# Robot-Main.net
KiCad netlist of a schematic drawn in Altium Designer
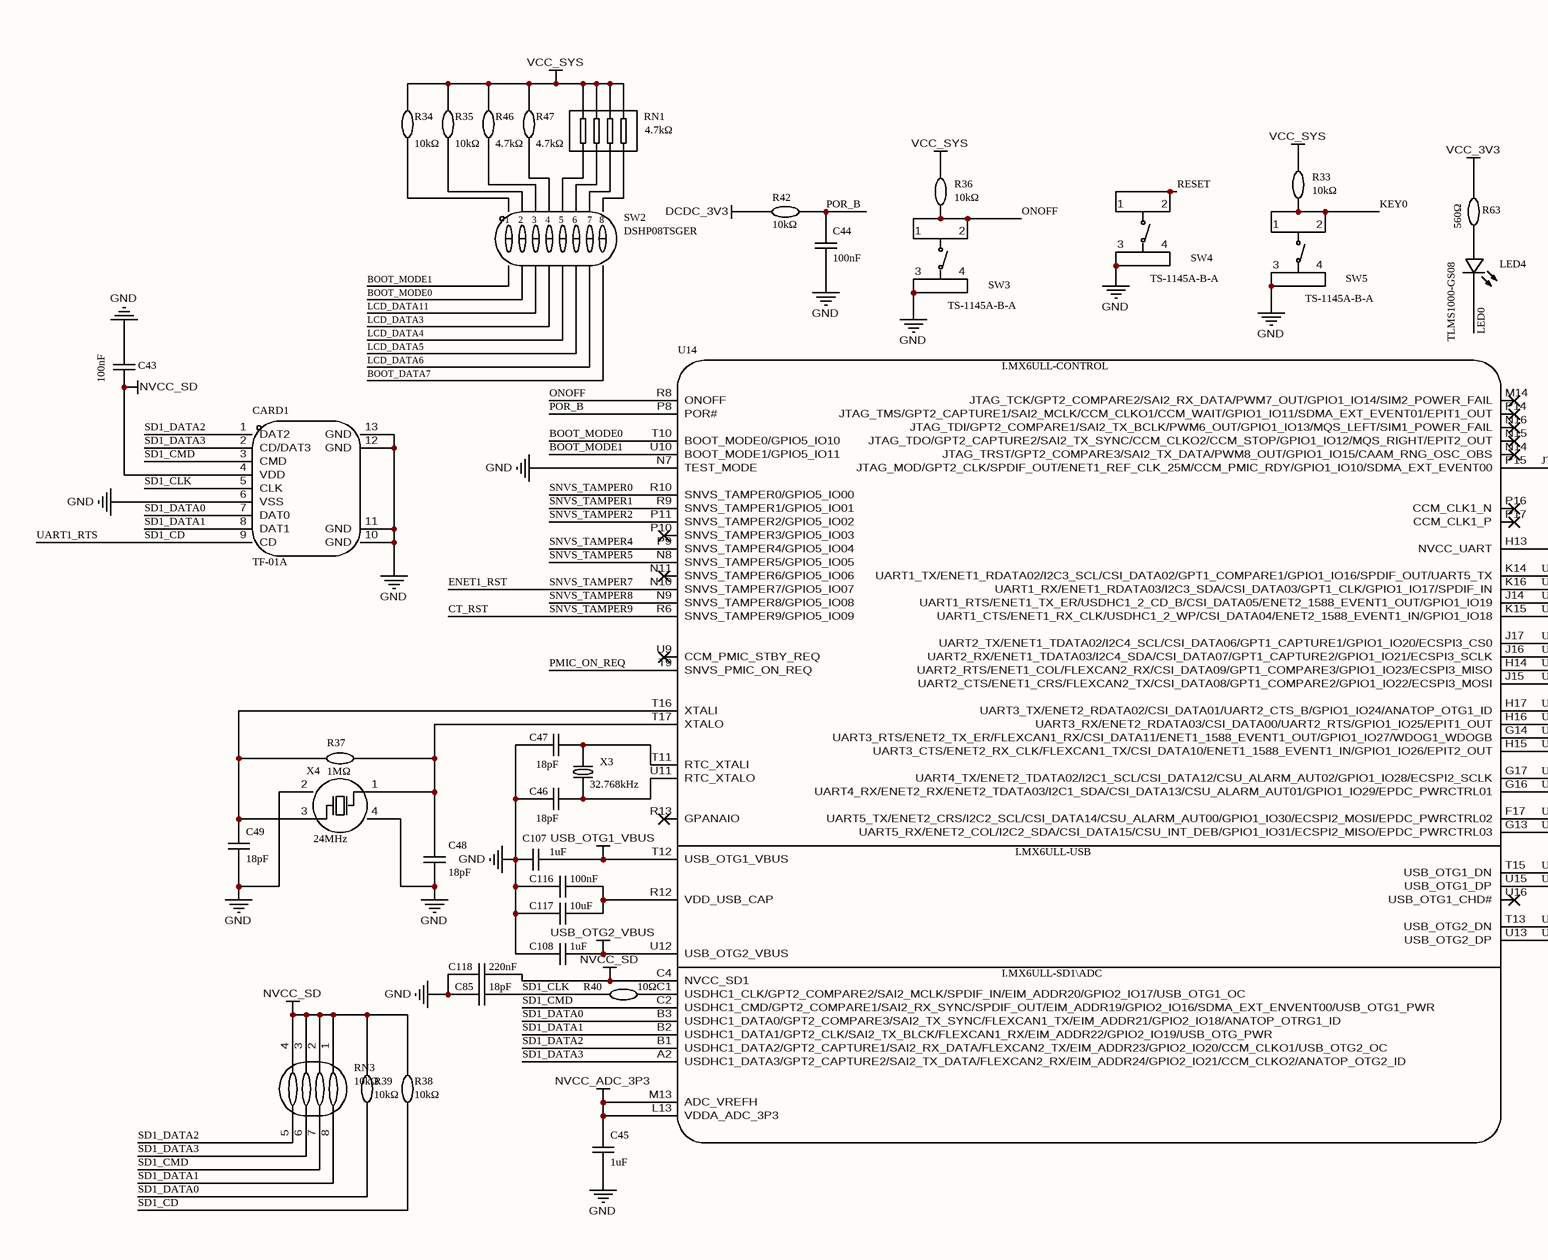
[diagram p0: Robot-Main.schdoc, left]
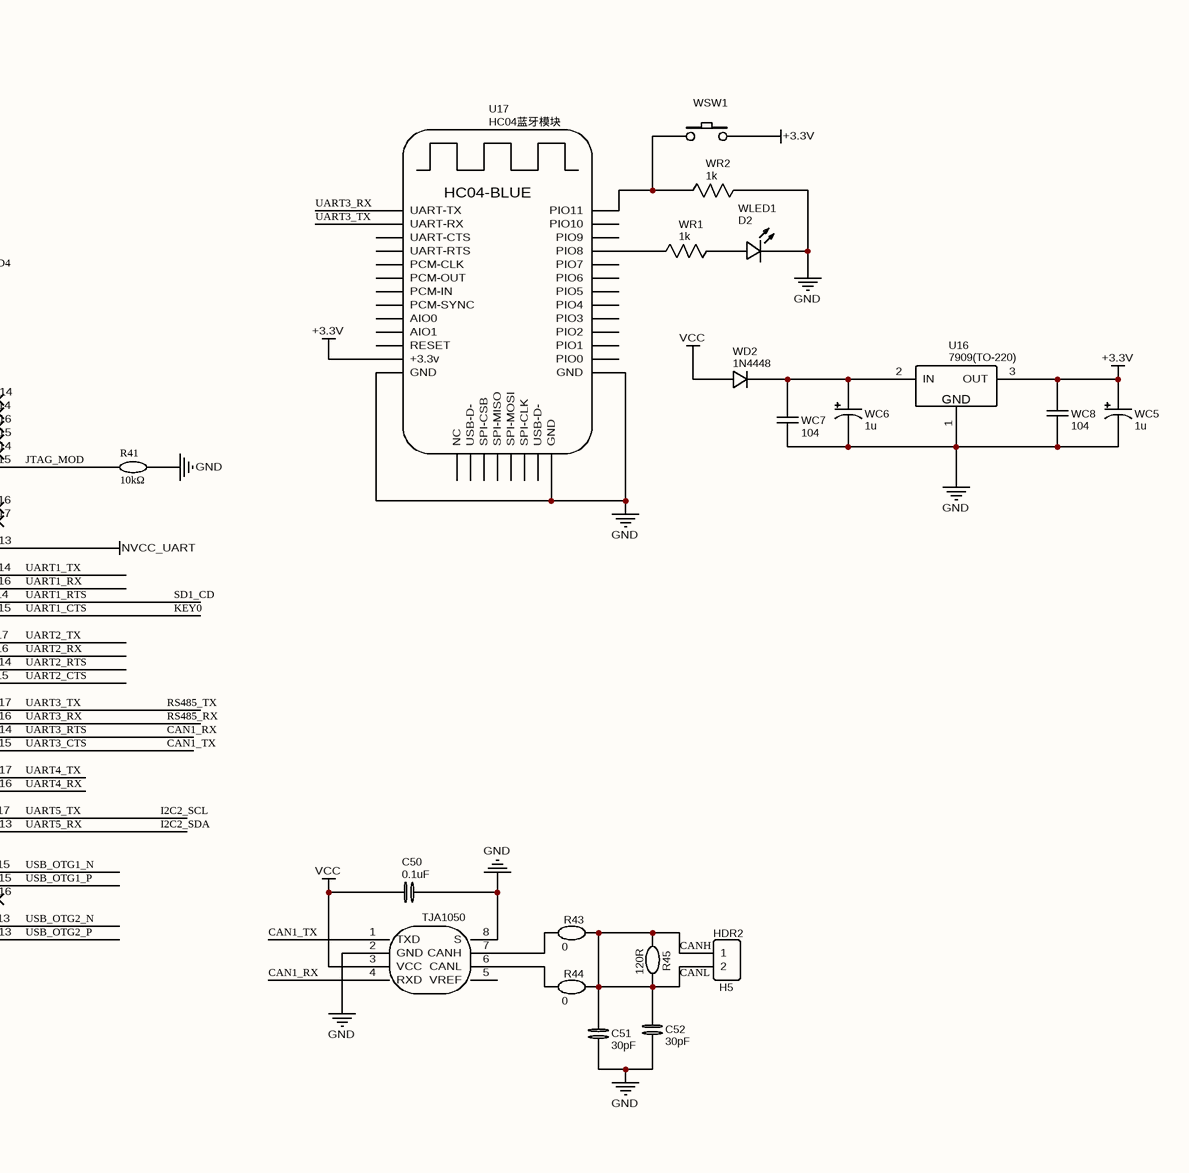
[diagram p1: Robot-Main.schdoc, right]

(export (version "E")
  (design (tool "Eeschema 10.0.6"))
  (components
    (comp (ref "C43")
      (value "100nF")
      (footprint "0")
      (fields
        (field (name "MANUFACTURER") "FH(风华)")
        (field (name "MANUFACTURER PART") "0402B104K160NT")
        (field (name "TOLERANCE") "±10%")
      )
      (libsource (lib "altium-import") (part "root_3_100nF_"))
    )
    (comp (ref "C44")
      (value "100nF")
      (footprint "0")
      (fields
        (field (name "MANUFACTURER") "FH(风华)")
        (field (name "MANUFACTURER PART") "0402B104K160NT")
        (field (name "TOLERANCE") "±10%")
      )
      (libsource (lib "altium-import") (part "root_3_100nF_"))
    )
    (comp (ref "C45")
      (value "1uF")
      (footprint "0")
      (fields
        (field (name "MANUFACTURER") "SAMSUNG(三星)")
        (field (name "MANUFACTURER PART") "CL05A105KP5NNNC")
        (field (name "TOLERANCE") "±10%")
      )
      (libsource (lib "altium-import") (part "root_1_1uF_"))
    )
    (comp (ref "C46")
      (value "18pF")
      (footprint "0")
      (fields
        (field (name "MANUFACTURER") "muRata(村田)")
        (field (name "MANUFACTURER PART") "GRM1555C1H180JA01D")
        (field (name "TOLERANCE") "±5%")
      )
      (libsource (lib "altium-import") (part "root_2_18pF_"))
    )
    (comp (ref "C47")
      (value "18pF")
      (footprint "0")
      (fields
        (field (name "MANUFACTURER") "muRata(村田)")
        (field (name "MANUFACTURER PART") "GRM1555C1H180JA01D")
        (field (name "TOLERANCE") "±5%")
      )
      (libsource (lib "altium-import") (part "root_2_18pF_"))
    )
    (comp (ref "C48")
      (value "18pF")
      (footprint "0")
      (fields
        (field (name "MANUFACTURER") "muRata(村田)")
        (field (name "MANUFACTURER PART") "GRM1555C1H180JA01D")
        (field (name "TOLERANCE") "±5%")
      )
      (libsource (lib "altium-import") (part "root_1_18pF_"))
    )
    (comp (ref "C49")
      (value "18pF")
      (footprint "0")
      (fields
        (field (name "MANUFACTURER") "muRata(村田)")
        (field (name "MANUFACTURER PART") "GRM1555C1H180JA01D")
        (field (name "TOLERANCE") "±5%")
      )
      (libsource (lib "altium-import") (part "root_1_18pF_"))
    )
    (comp (ref "C50")
      (value "0.1uF")
      (footprint "C0603")
      (fields (field (name "CONTRIBUTOR") "LCEDA_Lib"))
      (libsource (lib "altium-import") (part "root_0_0.1uF_"))
    )
    (comp (ref "C51")
      (value "30pF")
      (footprint "C0603")
      (fields (field (name "CONTRIBUTOR") "LCEDA_Lib"))
      (libsource (lib "altium-import") (part "root_1_30pF_"))
    )
    (comp (ref "C52")
      (value "30pF")
      (footprint "C0603")
      (fields (field (name "CONTRIBUTOR") "LCEDA_Lib"))
      (libsource (lib "altium-import") (part "root_1_30pF_"))
    )
    (comp (ref "C85")
      (value "18pF")
      (footprint "0")
      (fields
        (field (name "MANUFACTURER") "muRata(村田)")
        (field (name "MANUFACTURER PART") "GRM1555C1H180JA01D")
        (field (name "TOLERANCE") "±5%")
      )
      (libsource (lib "altium-import") (part "root_2_18pF_"))
    )
    (comp (ref "C107")
      (value "1uF")
      (footprint "0")
      (fields
        (field (name "MANUFACTURER") "SAMSUNG(三星)")
        (field (name "MANUFACTURER PART") "CL05A105KP5NNNC")
        (field (name "TOLERANCE") "±10%")
      )
      (libsource (lib "altium-import") (part "root_2_1uF_"))
    )
    (comp (ref "C108")
      (value "1uF")
      (footprint "0")
      (fields
        (field (name "MANUFACTURER") "SAMSUNG(三星)")
        (field (name "MANUFACTURER PART") "CL05A105KP5NNNC")
        (field (name "TOLERANCE") "±10%")
      )
      (libsource (lib "altium-import") (part "root_2_1uF_"))
    )
    (comp (ref "C116")
      (value "100nF")
      (footprint "0")
      (fields
        (field (name "MANUFACTURER") "FH(风华)")
        (field (name "MANUFACTURER PART") "0402B104K160NT")
        (field (name "TOLERANCE") "±10%")
      )
      (libsource (lib "altium-import") (part "root_0_100nF_"))
    )
    (comp (ref "C117")
      (value "10uF")
      (footprint "0")
      (fields
        (field (name "MANUFACTURER") "TAIYO YUDEN(太诱)")
        (field (name "MANUFACTURER PART") "JMK107BC6106MA-T")
        (field (name "TOLERANCE") "±20%")
      )
      (libsource (lib "altium-import") (part "root_2_10uF_"))
    )
    (comp (ref "C118")
      (value "220nF")
      (footprint "0")
      (fields
        (field (name "MANUFACTURER") "SAMSUNG(三星)")
        (field (name "MANUFACTURER PART") "CL05B224KO5NNNC")
        (field (name "TOLERANCE") "±10%")
      )
      (libsource (lib "altium-import") (part "root_2_220nF_"))
    )
    (comp (ref "CARD1")
      (value "TF-01A")
      (footprint "0")
      (fields (field (name "MANUFACTURER") "Yuandi(元迪)"))
      (libsource (lib "altium-import") (part "root_0_TF-01A_"))
    )
    (comp (ref "H5")
      (value "HDR2")
      (footprint "HDR-F-2.54_1X2")
      (fields (field (name "CONTRIBUTOR") "LCEDA_Lib"))
      (libsource (lib "altium-import") (part "root_0_HDR2_"))
    )
    (comp (ref "LED4")
      (value "TLMS1000-GS08")
      (footprint "0")
      (fields (field (name "MANUFACTURER") "VISHAY(威世)"))
      (libsource (lib "altium-import") (part "root_3_TLMS1000-GS08_"))
    )
    (comp (ref "R33")
      (value "10kΩ")
      (footprint "0")
      (fields
        (field (name "MANUFACTURER") "YAGEO(国巨)")
        (field (name "MANUFACTURER PART") "AC0402FR-0710KL")
        (field (name "TOLERANCE") "±1%")
      )
      (libsource (lib "altium-import") (part "root_3_10kΩ_"))
    )
    (comp (ref "R34")
      (value "10kΩ")
      (footprint "0")
      (fields
        (field (name "MANUFACTURER") "YAGEO(国巨)")
        (field (name "MANUFACTURER PART") "AC0402FR-0710KL")
        (field (name "TOLERANCE") "±1%")
      )
      (libsource (lib "altium-import") (part "root_1_10kΩ_"))
    )
    (comp (ref "R35")
      (value "10kΩ")
      (footprint "0")
      (fields
        (field (name "MANUFACTURER") "YAGEO(国巨)")
        (field (name "MANUFACTURER PART") "AC0402FR-0710KL")
        (field (name "TOLERANCE") "±1%")
      )
      (libsource (lib "altium-import") (part "root_1_10kΩ_"))
    )
    (comp (ref "R36")
      (value "10kΩ")
      (footprint "0")
      (fields
        (field (name "MANUFACTURER") "YAGEO(国巨)")
        (field (name "MANUFACTURER PART") "AC0402FR-0710KL")
        (field (name "TOLERANCE") "±1%")
      )
      (libsource (lib "altium-import") (part "root_3_10kΩ_"))
    )
    (comp (ref "R37")
      (value "1MΩ")
      (footprint "0")
      (fields
        (field (name "MANUFACTURER") "RESI(开步睿思）")
        (field (name "MANUFACTURER PART") "AECR0402F1M00K9")
        (field (name "TOLERANCE") "±1%")
      )
      (libsource (lib "altium-import") (part "root_0_1MΩ_"))
    )
    (comp (ref "R38")
      (value "10kΩ")
      (footprint "0")
      (fields
        (field (name "MANUFACTURER") "YAGEO(国巨)")
        (field (name "MANUFACTURER PART") "AC0402FR-0710KL")
        (field (name "TOLERANCE") "±1%")
      )
      (libsource (lib "altium-import") (part "root_1_10kΩ_"))
    )
    (comp (ref "R39")
      (value "10kΩ")
      (footprint "0")
      (fields
        (field (name "MANUFACTURER") "YAGEO(国巨)")
        (field (name "MANUFACTURER PART") "AC0402FR-0710KL")
        (field (name "TOLERANCE") "±1%")
      )
      (libsource (lib "altium-import") (part "root_1_10kΩ_"))
    )
    (comp (ref "R40")
      (value "10Ω")
      (footprint "0")
      (fields
        (field (name "MANUFACTURER") "YAGEO(国巨)")
        (field (name "MANUFACTURER PART") "RC0402FR-0710RL")
        (field (name "TOLERANCE") "±1%")
      )
      (libsource (lib "altium-import") (part "root_0_10Ω_"))
    )
    (comp (ref "R41")
      (value "10kΩ")
      (footprint "0")
      (fields
        (field (name "MANUFACTURER") "YAGEO(国巨)")
        (field (name "MANUFACTURER PART") "AC0402FR-0710KL")
        (field (name "TOLERANCE") "±1%")
      )
      (libsource (lib "altium-import") (part "root_2_10kΩ_"))
    )
    (comp (ref "R42")
      (value "10kΩ")
      (footprint "0")
      (fields
        (field (name "MANUFACTURER") "YAGEO(国巨)")
        (field (name "MANUFACTURER PART") "AC0402FR-0710KL")
        (field (name "TOLERANCE") "±1%")
      )
      (libsource (lib "altium-import") (part "root_2_10kΩ_"))
    )
    (comp (ref "R43")
      (value "0")
      (footprint "R0603")
      (fields (field (name "CONTRIBUTOR") "LCEDA_Lib"))
      (libsource (lib "altium-import") (part "root_0_0_"))
    )
    (comp (ref "R44")
      (value "0")
      (footprint "R0603")
      (fields (field (name "CONTRIBUTOR") "LCEDA_Lib"))
      (libsource (lib "altium-import") (part "root_0_0_"))
    )
    (comp (ref "R45")
      (value "120R")
      (footprint "R0603")
      (fields (field (name "CONTRIBUTOR") "LCEDA_Lib"))
      (libsource (lib "altium-import") (part "root_1_120R_"))
    )
    (comp (ref "R46")
      (value "4.7kΩ")
      (footprint "0")
      (fields
        (field (name "MANUFACTURER") "UNI-ROYAL(厚声)")
        (field (name "MANUFACTURER PART") "0402WGF4701TCE")
        (field (name "TOLERANCE") "±1%")
      )
      (libsource (lib "altium-import") (part "root_1_4.7kΩ_"))
    )
    (comp (ref "R47")
      (value "4.7kΩ")
      (footprint "0")
      (fields
        (field (name "MANUFACTURER") "UNI-ROYAL(厚声)")
        (field (name "MANUFACTURER PART") "0402WGF4701TCE")
        (field (name "TOLERANCE") "±1%")
      )
      (libsource (lib "altium-import") (part "root_1_4.7kΩ_"))
    )
    (comp (ref "R63")
      (value "560Ω")
      (footprint "0")
      (fields
        (field (name "MANUFACTURER") "PANASONIC(松下)")
        (field (name "MANUFACTURER PART") "ERJ2RKF5600X")
        (field (name "TOLERANCE") "±1%")
      )
      (libsource (lib "altium-import") (part "root_3_560Ω_"))
    )
    (comp (ref "RN1")
      (value "4.7kΩ")
      (footprint "0")
      (fields (field (name "MANUFACTURER") "RALEC(旺诠)") (field (name "MANUFACTURER PART") "RTA02-4D472JTH"))
      (libsource (lib "altium-import") (part "root_2_4.7kΩ_"))
    )
    (comp (ref "RN3")
      (value "10kΩ")
      (footprint "0")
      (fields (field (name "MANUFACTURER") "YAGEO(国巨)") (field (name "MANUFACTURER PART") "YC124-JR-0710KL"))
      (libsource (lib "") (part "root_2_10kΩ__1"))
    )
    (comp (ref "SW2")
      (value "DSHP08TSGER")
      (footprint "0")
      (fields (field (name "MANUFACTURER") "康深"))
      (libsource (lib "altium-import") (part "root_2_DSHP08TSGER_"))
    )
    (comp (ref "SW3")
      (value "TS-1145A-B-A")
      (footprint "0")
      (fields (field (name "MANUFACTURER") "XKB Connectivity(中国星坤)"))
      (libsource (lib "altium-import") (part "root_0_TS-1145A-B-A_"))
    )
    (comp (ref "SW4")
      (value "TS-1145A-B-A")
      (footprint "0")
      (fields (field (name "MANUFACTURER") "XKB Connectivity(中国星坤)"))
      (libsource (lib "altium-import") (part "root_0_TS-1145A-B-A_"))
    )
    (comp (ref "SW5")
      (value "TS-1145A-B-A")
      (footprint "0")
      (fields (field (name "MANUFACTURER") "XKB Connectivity(中国星坤)"))
      (libsource (lib "altium-import") (part "root_0_TS-1145A-B-A_"))
    )
    (comp (ref "U14")
      (value "MCIMX6Y2CVM08AB")
      (footprint "0")
      (fields (field (name "MANUFACTURER") "NXP(恩智浦)") (field (name "MANUFACTURER PART") "MCIMX6Y2CVM05AB"))
      (libsource (lib "altium-import") (part "root_0_MCIMX6Y2CVM08AB_"))
    )
    (comp (ref "U15")
      (value "TJA1050")
      (footprint "SOIC-8_L5.0-W4.0-P1.27-LS6.0-BL")
      (fields (field (name "MANUFACTURER") "NXP") (field (name "MANUFACTURER PART") "TJA1050T/CM,118"))
      (libsource (lib "altium-import") (part "root_0_TJA1050_"))
    )
    (comp (ref "U16")
      (value "7909(TO-220)")
      (footprint "TO-220IS_L10.16-W4.7-P2.54-L")
      (fields
        (field (name "MANUFACTURER") "KEC Semicon")
        (field (name "MANUFACTURER PART") "KIA7909PI-U/PF")
        (field (name "CONTRIBUTOR") "LCEDA_Lib")
      )
      (libsource (lib "altium-import") (part "root_0_7909(TO-220)_"))
    )
    (comp (ref "U17")
      (value "HC04蓝牙模块")
      (fields (field (name "CONTRIBUTOR") "wls20010228"))
      (libsource (lib "altium-import") (part "root_0_HC04蓝牙模块_"))
    )
    (comp (ref "WC5")
      (value "1u")
      (footprint "CAP-D3.0XF1.5")
      (libsource (lib "altium-import") (part "root_0_1u_"))
    )
    (comp (ref "WC6")
      (value "1u")
      (footprint "CAP-D3.0XF1.5")
      (libsource (lib "altium-import") (part "root_0_1u_"))
    )
    (comp (ref "WC7")
      (value "104")
      (footprint "RAD-0.1")
      (libsource (lib "altium-import") (part "root_0_104_"))
    )
    (comp (ref "WC8")
      (value "104")
      (footprint "RAD-0.1")
      (libsource (lib "altium-import") (part "root_0_104_"))
    )
    (comp (ref "WD2")
      (value "1N4448")
      (footprint "DO-35")
      (fields (field (name "MANUFACTURER") "SEMTECH"))
      (libsource (lib "altium-import") (part "root_0_1N4448_"))
    )
    (comp (ref "WLED1")
      (value "D2")
      (footprint "LED-3MM/2.54")
      (fields
        (field (name "MANUFACTURER") "EVERLIGHT")
        (field (name "MANUFACTURER PART") "204-10SURD/S530-A3")
      )
      (libsource (lib "altium-import") (part "root_0_D2_"))
    )
    (comp (ref "WR1")
      (value "1k")
      (footprint "AXIAL-0.3")
      (libsource (lib "altium-import") (part "root_0_1k_"))
    )
    (comp (ref "WR2")
      (value "1k")
      (footprint "AXIAL-0.3")
      (libsource (lib "altium-import") (part "root_0_1k_"))
    )
    (comp (ref "WSW1")
      (value "EVQ22705R")
      (footprint "KEY-6.0*6.0-4")
      (fields (field (name "MANUFACTURER") "PANASONIC") (field (name "CONTRIBUTOR") "LCSC"))
      (libsource (lib "altium-import") (part "root_0_EVQ22705R_"))
    )
    (comp (ref "X3")
      (value "32.768kHz")
      (footprint "0")
      (fields (field (name "MANUFACTURER") "EPSON(爱普生)") (field (name "MANUFACTURER PART") "Q13FC1350000400"))
      (libsource (lib "altium-import") (part "root_1_32.768kHz_"))
    )
    (comp (ref "X4")
      (value "24MHz")
      (footprint "0")
      (fields (field (name "MANUFACTURER") "EPSON(爱普生)") (field (name "MANUFACTURER PART") "X1E0000210128"))
      (libsource (lib "altium-import") (part "root_2_24MHz_"))
    )
  )
  (nets
    (net (code "1") (name "+3.3V") (class "Default")
      (node (ref "U16") (pin "3") (pinfunction "OUT_3") (pintype "passive"))
      (node (ref "U17") (pin "15") (pinfunction "+3.3v_15") (pintype "passive"))
      (node (ref "WC5") (pin "1") (pinfunction "1_1") (pintype "passive"))
      (node (ref "WC8") (pin "2") (pinfunction "2_2") (pintype "passive"))
      (node (ref "WSW1") (pin "2") (pinfunction "2_2") (pintype "passive"))
    )
    (net (code "2") (name "/BOOT_DATA7") (class "Default")
      (node (ref "SW2") (pin "16") (pinfunction "16_16") (pintype "passive"))
    )
    (net (code "3") (name "/BOOT_MODE0") (class "Default")
      (node (ref "SW2") (pin "10") (pinfunction "PIN10_10") (pintype "passive"))
      (node (ref "U14") (pin "T10") (pinfunction "BOOT_MODE0/GPIO5_IO10_T10") (pintype "passive"))
    )
    (net (code "4") (name "/BOOT_MODE1") (class "Default")
      (node (ref "SW2") (pin "9") (pinfunction "PIN9_9") (pintype "passive"))
      (node (ref "U14") (pin "U10") (pinfunction "BOOT_MODE1/GPIO5_IO11_U10") (pintype "passive"))
    )
    (net (code "5") (name "/CAN1_RX") (class "Default")
      (node (ref "U14") (pin "G14") (pinfunction "UART3_RTS/ENET2_TX_ER/FLEXCAN1_RX/CSI_DATA11/ENET1_1588_EVENT1_OUT/GPIO1_IO27/WDOG1_WDOGB_G14") (pintype "passive"))
      (node (ref "U15") (pin "4") (pinfunction "RXD_4") (pintype "passive"))
    )
    (net (code "6") (name "/CAN1_TX") (class "Default")
      (node (ref "U14") (pin "H15") (pinfunction "UART3_CTS/ENET2_RX_CLK/FLEXCAN1_TX/CSI_DATA10/ENET1_1588_EVENT1_IN/GPIO1_IO26/EPIT2_OUT_H15") (pintype "passive"))
      (node (ref "U15") (pin "1") (pinfunction "TXD_1") (pintype "passive"))
    )
    (net (code "7") (name "/CANH") (class "Default")
      (node (ref "C51") (pin "2") (pinfunction "2_2") (pintype "passive"))
      (node (ref "C52") (pin "2") (pinfunction "2_2") (pintype "passive"))
      (node (ref "H5") (pin "1") (pinfunction "1_1") (pintype "passive"))
      (node (ref "H5") (pin "2") (pinfunction "2_2") (pintype "passive"))
      (node (ref "R43") (pin "2") (pinfunction "2_2") (pintype "passive"))
      (node (ref "R44") (pin "2") (pinfunction "2_2") (pintype "passive"))
      (node (ref "R45") (pin "1") (pinfunction "1_1") (pintype "passive"))
      (node (ref "R45") (pin "2") (pinfunction "2_2") (pintype "passive"))
    )
    (net (code "8") (name "/CT_RST") (class "Default")
      (node (ref "U14") (pin "R6") (pinfunction "SNVS_TAMPER9/GPIO5_IO09_R6") (pintype "passive"))
    )
    (net (code "9") (name "/ENET1_RST") (class "Default")
      (node (ref "U14") (pin "N10") (pinfunction "SNVS_TAMPER7/GPIO5_IO07_N10") (pintype "passive"))
    )
    (net (code "10") (name "/I2C2_SCL") (class "Default")
      (node (ref "U14") (pin "F17") (pinfunction "UART5_TX/ENET2_CRS/I2C2_SCL/CSI_DATA14/CSU_ALARM_AUT00/GPIO1_IO30/ECSPI2_MOSI/EPDC_PWRCTRL02_F17") (pintype "passive"))
    )
    (net (code "11") (name "/I2C2_SDA") (class "Default")
      (node (ref "U14") (pin "G13") (pinfunction "UART5_RX/ENET2_COL/I2C2_SDA/CSI_DATA15/CSU_INT_DEB/GPIO1_IO31/ECSPI2_MISO/EPDC_PWRCTRL03_G13") (pintype "passive"))
    )
    (net (code "12") (name "/JTAG_MOD") (class "Default")
      (node (ref "R41") (pin "2") (pinfunction "2_2") (pintype "passive"))
      (node (ref "U14") (pin "P15") (pinfunction "JTAG_MOD/GPT2_CLK/SPDIF_OUT/ENET1_REF_CLK_25M/CCM_PMIC_RDY/GPIO1_IO10/SDMA_EXT_EVENT00_P15") (pintype "passive"))
    )
    (net (code "13") (name "/KEY0") (class "Default")
      (node (ref "R33") (pin "2") (pinfunction "2_2") (pintype "passive"))
      (node (ref "SW5") (pin "1") (pinfunction "1_1") (pintype "passive"))
      (node (ref "SW5") (pin "2") (pinfunction "2_2") (pintype "passive"))
      (node (ref "U14") (pin "K15") (pinfunction "UART1_CTS/ENET1_RX_CLK/USDHC1_2_WP/CSI_DATA04/ENET2_1588_EVENT1_IN/GPIO1_IO18_K15") (pintype "passive"))
    )
    (net (code "14") (name "/LCD_DATA3") (class "Default")
      (node (ref "SW2") (pin "12") (pinfunction "PIN12_12") (pintype "passive"))
    )
    (net (code "15") (name "/LCD_DATA4") (class "Default")
      (node (ref "SW2") (pin "13") (pinfunction "PIN13_13") (pintype "passive"))
    )
    (net (code "16") (name "/LCD_DATA5") (class "Default")
      (node (ref "SW2") (pin "14") (pinfunction "PIN14_14") (pintype "passive"))
    )
    (net (code "17") (name "/LCD_DATA6") (class "Default")
      (node (ref "SW2") (pin "15") (pinfunction "15_15") (pintype "passive"))
    )
    (net (code "18") (name "/LCD_DATA11") (class "Default")
      (node (ref "SW2") (pin "11") (pinfunction "PIN11_11") (pintype "passive"))
    )
    (net (code "19") (name "/LED0") (class "Default")
      (node (ref "LED4") (pin "2") (pinfunction "K_2") (pintype "passive"))
    )
    (net (code "20") (name "/ONOFF") (class "Default")
      (node (ref "R36") (pin "2") (pinfunction "2_2") (pintype "passive"))
      (node (ref "SW3") (pin "1") (pinfunction "1_1") (pintype "passive"))
      (node (ref "SW3") (pin "2") (pinfunction "2_2") (pintype "passive"))
      (node (ref "U14") (pin "R8") (pinfunction "ONOFF_R8") (pintype "passive"))
    )
    (net (code "21") (name "/PMIC_ON_REQ") (class "Default")
      (node (ref "U14") (pin "T9") (pinfunction "SNVS_PMIC_ON_REQ_T9") (pintype "passive"))
    )
    (net (code "22") (name "/POR_B") (class "Default")
      (node (ref "C44") (pin "1") (pinfunction "1_1") (pintype "passive"))
      (node (ref "R42") (pin "1") (pinfunction "1_1") (pintype "passive"))
      (node (ref "U14") (pin "P8") (pinfunction "POR#_P8") (pintype "passive"))
    )
    (net (code "23") (name "/RESET") (class "Default")
      (node (ref "SW4") (pin "1") (pinfunction "1_1") (pintype "passive"))
      (node (ref "SW4") (pin "2") (pinfunction "2_2") (pintype "passive"))
    )
    (net (code "24") (name "/RS485_RX") (class "Default")
      (node (ref "U14") (pin "H16") (pinfunction "UART3_RX/ENET2_RDATA03/CSI_DATA00/UART2_RTS/GPIO1_IO25/EPIT1_OUT_H16") (pintype "passive"))
      (node (ref "U17") (pin "27") (pinfunction "UART-TX_27") (pintype "passive"))
    )
    (net (code "25") (name "/RS485_TX") (class "Default")
      (node (ref "U14") (pin "H17") (pinfunction "UART3_TX/ENET2_RDATA02/CSI_DATA01/UART2_CTS_B/GPIO1_IO24/ANATOP_OTG1_ID_H17") (pintype "passive"))
      (node (ref "U17") (pin "26") (pinfunction "UART-RX_26") (pintype "passive"))
    )
    (net (code "26") (name "/SD1_CD") (class "Default")
      (node (ref "CARD1") (pin "9") (pinfunction "CD_9") (pintype "passive"))
      (node (ref "R38") (pin "1") (pinfunction "1_1") (pintype "passive"))
      (node (ref "U14") (pin "J14") (pinfunction "UART1_RTS/ENET1_TX_ER/USDHC1_2_CD_B/CSI_DATA05/ENET2_1588_EVENT1_OUT/GPIO1_IO19_J14") (pintype "passive"))
    )
    (net (code "27") (name "/SD1_CLK") (class "Default")
      (node (ref "C85") (pin "1") (pinfunction "1_1") (pintype "passive"))
      (node (ref "CARD1") (pin "5") (pinfunction "CLK_5") (pintype "passive"))
      (node (ref "R40") (pin "1") (pinfunction "1_1") (pintype "passive"))
    )
    (net (code "28") (name "/SD1_CMD") (class "Default")
      (node (ref "CARD1") (pin "3") (pinfunction "CMD_3") (pintype "passive"))
      (node (ref "RN3") (pin "7") (pinfunction "7_7") (pintype "passive"))
      (node (ref "U14") (pin "C2") (pinfunction "USDHC1_CMD/GPT2_COMPARE1/SAI2_RX_SYNC/SPDIF_OUT/EIM_ADDR19/GPIO2_IO16/SDMA_EXT_ENVENT00/USB_OTG1_PWR_C2") (pintype "passive"))
    )
    (net (code "29") (name "/SD1_DATA0") (class "Default")
      (node (ref "CARD1") (pin "7") (pinfunction "DAT0_7") (pintype "passive"))
      (node (ref "R39") (pin "1") (pinfunction "1_1") (pintype "passive"))
      (node (ref "U14") (pin "B3") (pinfunction "USDHC1_DATA0/GPT2_COMPARE3/SAI2_TX_SYNC/FLEXCAN1_TX/EIM_ADDR21/GPIO2_IO18/ANATOP_OTRG1_ID_B3") (pintype "passive"))
    )
    (net (code "30") (name "/SD1_DATA1") (class "Default")
      (node (ref "CARD1") (pin "8") (pinfunction "DAT1_8") (pintype "passive"))
      (node (ref "RN3") (pin "8") (pinfunction "8_8") (pintype "passive"))
      (node (ref "U14") (pin "B2") (pinfunction "USDHC1_DATA1/GPT2_CLK/SAI2_TX_BLCK/FLEXCAN1_RX/EIM_ADDR22/GPIO2_IO19/USB_OTG_PWR_B2") (pintype "passive"))
    )
    (net (code "31") (name "/SD1_DATA2") (class "Default")
      (node (ref "CARD1") (pin "1") (pinfunction "DAT2_1") (pintype "passive"))
      (node (ref "RN3") (pin "5") (pinfunction "5_5") (pintype "passive"))
      (node (ref "U14") (pin "B1") (pinfunction "USDHC1_DATA2/GPT2_CAPTURE1/SAI2_RX_DATA/FLEXCAN2_TX/EIM_ADDR23/GPIO2_IO20/CCM_CLKO1/USB_OTG2_OC_B1") (pintype "passive"))
    )
    (net (code "32") (name "/SD1_DATA3") (class "Default")
      (node (ref "CARD1") (pin "2") (pinfunction "CD/DAT3_2") (pintype "passive"))
      (node (ref "RN3") (pin "6") (pinfunction "6_6") (pintype "passive"))
      (node (ref "U14") (pin "A2") (pinfunction "USDHC1_DATA3/GPT2_CAPTURE2/SAI2_TX_DATA/FLEXCAN2_RX/EIM_ADDR24/GPIO2_IO21/CCM_CLKO2/ANATOP_OTG2_ID_A2") (pintype "passive"))
    )
    (net (code "33") (name "/SNVS_TAMPER0") (class "Default")
      (node (ref "U14") (pin "R10") (pinfunction "SNVS_TAMPER0/GPIO5_IO00_R10") (pintype "passive"))
    )
    (net (code "34") (name "/SNVS_TAMPER1") (class "Default")
      (node (ref "U14") (pin "R9") (pinfunction "SNVS_TAMPER1/GPIO5_IO01_R9") (pintype "passive"))
    )
    (net (code "35") (name "/SNVS_TAMPER2") (class "Default")
      (node (ref "U14") (pin "P11") (pinfunction "SNVS_TAMPER2/GPIO5_IO02_P11") (pintype "passive"))
    )
    (net (code "36") (name "/SNVS_TAMPER4") (class "Default")
      (node (ref "U14") (pin "P9") (pinfunction "SNVS_TAMPER4/GPIO5_IO04_P9") (pintype "passive"))
    )
    (net (code "37") (name "/SNVS_TAMPER5") (class "Default")
      (node (ref "U14") (pin "N8") (pinfunction "SNVS_TAMPER5/GPIO5_IO05_N8") (pintype "passive"))
    )
    (net (code "38") (name "/SNVS_TAMPER8") (class "Default")
      (node (ref "U14") (pin "N9") (pinfunction "SNVS_TAMPER8/GPIO5_IO08_N9") (pintype "passive"))
    )
    (net (code "39") (name "/UART1_RX") (class "Default")
      (node (ref "U14") (pin "K16") (pinfunction "UART1_RX/ENET1_RDATA03/I2C3_SDA/CSI_DATA03/GPT1_CLK/GPIO1_IO17/SPDIF_IN_K16") (pintype "passive"))
    )
    (net (code "40") (name "/UART1_TX") (class "Default")
      (node (ref "U14") (pin "K14") (pinfunction "UART1_TX/ENET1_RDATA02/I2C3_SCL/CSI_DATA02/GPT1_COMPARE1/GPIO1_IO16/SPDIF_OUT/UART5_TX_K14") (pintype "passive"))
    )
    (net (code "41") (name "/UART2_CTS") (class "Default")
      (node (ref "U14") (pin "J15") (pinfunction "UART2_CTS/ENET1_CRS/FLEXCAN2_TX/CSI_DATA08/GPT1_COMPARE2/GPIO1_IO22/ECSPI3_MOSI_J15") (pintype "passive"))
    )
    (net (code "42") (name "/UART2_RTS") (class "Default")
      (node (ref "U14") (pin "H14") (pinfunction "UART2_RTS/ENET1_COL/FLEXCAN2_RX/CSI_DATA09/GPT1_COMPARE3/GPIO1_IO23/ECSPI3_MISO_H14") (pintype "passive"))
    )
    (net (code "43") (name "/UART2_RX") (class "Default")
      (node (ref "U14") (pin "J16") (pinfunction "UART2_RX/ENET1_TDATA03/I2C4_SDA/CSI_DATA07/GPT1_CAPTURE2/GPIO1_IO21/ECSPI3_SCLK_J16") (pintype "passive"))
    )
    (net (code "44") (name "/UART2_TX") (class "Default")
      (node (ref "U14") (pin "J17") (pinfunction "UART2_TX/ENET1_TDATA02/I2C4_SCL/CSI_DATA06/GPT1_CAPTURE1/GPIO1_IO20/ECSPI3_CS0_J17") (pintype "passive"))
    )
    (net (code "45") (name "/UART4_RX") (class "Default")
      (node (ref "U14") (pin "G16") (pinfunction "UART4_RX/ENET2_RX/ENET2_TDATA03/I2C1_SDA/CSI_DATA13/CSU_ALARM_AUT01/GPIO1_IO29/EPDC_PWRCTRL01_G16") (pintype "passive"))
    )
    (net (code "46") (name "/UART4_TX") (class "Default")
      (node (ref "U14") (pin "G17") (pinfunction "UART4_TX/ENET2_TDATA02/I2C1_SCL/CSI_DATA12/CSU_ALARM_AUT02/GPIO1_IO28/ECSPI2_SCLK_G17") (pintype "passive"))
    )
    (net (code "47") (name "/USB_OTG1_N") (class "Default")
      (node (ref "U14") (pin "T15") (pinfunction "USB_OTG1_DN_T15") (pintype "passive"))
    )
    (net (code "48") (name "/USB_OTG1_P") (class "Default")
      (node (ref "U14") (pin "U15") (pinfunction "USB_OTG1_DP_U15") (pintype "passive"))
    )
    (net (code "49") (name "/USB_OTG2_N") (class "Default")
      (node (ref "U14") (pin "T13") (pinfunction "USB_OTG2_DN_T13") (pintype "passive"))
    )
    (net (code "50") (name "/USB_OTG2_P") (class "Default")
      (node (ref "U14") (pin "U13") (pinfunction "USB_OTG2_DP_U13") (pintype "passive"))
    )
    (net (code "51") (name "DCDC_3V3") (class "Default")
      (node (ref "R42") (pin "2") (pinfunction "2_2") (pintype "passive"))
    )
    (net (code "52") (name "GND") (class "Default")
      (node (ref "C107") (pin "2") (pinfunction "2_2") (pintype "passive"))
      (node (ref "C108") (pin "2") (pinfunction "2_2") (pintype "passive"))
      (node (ref "C116") (pin "1") (pinfunction "1_1") (pintype "passive"))
      (node (ref "C117") (pin "2") (pinfunction "2_2") (pintype "passive"))
      (node (ref "C118") (pin "2") (pinfunction "2_2") (pintype "passive"))
      (node (ref "C43") (pin "1") (pinfunction "1_1") (pintype "passive"))
      (node (ref "C44") (pin "2") (pinfunction "2_2") (pintype "passive"))
      (node (ref "C45") (pin "1") (pinfunction "1_1") (pintype "passive"))
      (node (ref "C46") (pin "2") (pinfunction "2_2") (pintype "passive"))
      (node (ref "C47") (pin "2") (pinfunction "2_2") (pintype "passive"))
      (node (ref "C48") (pin "1") (pinfunction "1_1") (pintype "passive"))
      (node (ref "C49") (pin "1") (pinfunction "1_1") (pintype "passive"))
      (node (ref "C50") (pin "2") (pinfunction "2_2") (pintype "passive"))
      (node (ref "C51") (pin "1") (pinfunction "1_1") (pintype "passive"))
      (node (ref "C52") (pin "1") (pinfunction "1_1") (pintype "passive"))
      (node (ref "C85") (pin "2") (pinfunction "2_2") (pintype "passive"))
      (node (ref "CARD1") (pin "10") (pinfunction "GND_10") (pintype "passive"))
      (node (ref "CARD1") (pin "11") (pinfunction "GND_11") (pintype "passive"))
      (node (ref "CARD1") (pin "12") (pinfunction "GND_12") (pintype "passive"))
      (node (ref "CARD1") (pin "13") (pinfunction "GND_13") (pintype "passive"))
      (node (ref "CARD1") (pin "6") (pinfunction "VSS_6") (pintype "passive"))
      (node (ref "R41") (pin "1") (pinfunction "1_1") (pintype "passive"))
      (node (ref "SW3") (pin "3") (pinfunction "3_3") (pintype "passive"))
      (node (ref "SW3") (pin "4") (pinfunction "4_4") (pintype "passive"))
      (node (ref "SW4") (pin "3") (pinfunction "3_3") (pintype "passive"))
      (node (ref "SW4") (pin "4") (pinfunction "4_4") (pintype "passive"))
      (node (ref "SW5") (pin "3") (pinfunction "3_3") (pintype "passive"))
      (node (ref "SW5") (pin "4") (pinfunction "4_4") (pintype "passive"))
      (node (ref "U14") (pin "N7") (pinfunction "TEST_MODE_N7") (pintype "passive"))
      (node (ref "U15") (pin "2") (pinfunction "GND_2") (pintype "passive"))
      (node (ref "U15") (pin "8") (pinfunction "S_8") (pintype "passive"))
      (node (ref "U16") (pin "1") (pinfunction "GND_1") (pintype "passive"))
      (node (ref "U17") (pin "14") (pinfunction "GND_14") (pintype "passive"))
      (node (ref "U17") (pin "28") (pinfunction "GND_28") (pintype "passive"))
      (node (ref "U17") (pin "36") (pinfunction "GND_36") (pintype "passive"))
      (node (ref "WC5") (pin "2") (pinfunction "2_2") (pintype "passive"))
      (node (ref "WC6") (pin "2") (pinfunction "2_2") (pintype "passive"))
      (node (ref "WC7") (pin "1") (pinfunction "1_1") (pintype "passive"))
      (node (ref "WC8") (pin "1") (pinfunction "1_1") (pintype "passive"))
      (node (ref "WLED1") (pin "2") (pinfunction "K_2") (pintype "passive"))
      (node (ref "WR2") (pin "2") (pinfunction "2_2") (pintype "passive"))
      (node (ref "X4") (pin "2") (pinfunction "GND_2") (pintype "passive"))
      (node (ref "X4") (pin "4") (pinfunction "GND_4") (pintype "passive"))
    )
    (net (code "53") (name "NVCC_ADC_3P3") (class "Default")
      (node (ref "C45") (pin "2") (pinfunction "2_2") (pintype "passive"))
      (node (ref "U14") (pin "L13") (pinfunction "VDDA_ADC_3P3_L13") (pintype "passive"))
      (node (ref "U14") (pin "M13") (pinfunction "ADC_VREFH_M13") (pintype "passive"))
    )
    (net (code "54") (name "NVCC_SD") (class "Default")
      (node (ref "C118") (pin "1") (pinfunction "1_1") (pintype "passive"))
      (node (ref "C43") (pin "2") (pinfunction "2_2") (pintype "passive"))
      (node (ref "CARD1") (pin "4") (pinfunction "VDD_4") (pintype "passive"))
      (node (ref "R38") (pin "2") (pinfunction "2_2") (pintype "passive"))
      (node (ref "R39") (pin "2") (pinfunction "2_2") (pintype "passive"))
      (node (ref "RN3") (pin "1") (pinfunction "1_1") (pintype "passive"))
      (node (ref "RN3") (pin "2") (pinfunction "2_2") (pintype "passive"))
      (node (ref "RN3") (pin "3") (pinfunction "3_3") (pintype "passive"))
      (node (ref "RN3") (pin "4") (pinfunction "4_4") (pintype "passive"))
      (node (ref "U14") (pin "C4") (pinfunction "NVCC_SD1_C4") (pintype "passive"))
    )
    (net (code "55") (name "NVCC_UART") (class "Default")
      (node (ref "U14") (pin "H13") (pinfunction "NVCC_UART_H13") (pintype "passive"))
    )
    (net (code "56") (name "Net-(LED4-A)") (class "Default")
      (node (ref "LED4") (pin "1") (pinfunction "A_1") (pintype "passive"))
      (node (ref "R63") (pin "2") (pinfunction "2_2") (pintype "passive"))
    )
    (net (code "57") (name "Net-(SW2-PIN1)") (class "Default")
      (node (ref "R34") (pin "1") (pinfunction "1_1") (pintype "passive"))
      (node (ref "SW2") (pin "1") (pinfunction "PIN1_1") (pintype "passive"))
    )
    (net (code "58") (name "Net-(SW2-PIN2)") (class "Default")
      (node (ref "R35") (pin "1") (pinfunction "1_1") (pintype "passive"))
      (node (ref "SW2") (pin "2") (pinfunction "PIN2_2") (pintype "passive"))
    )
    (net (code "59") (name "Net-(SW2-PIN3)") (class "Default")
      (node (ref "R46") (pin "1") (pinfunction "1_1") (pintype "passive"))
      (node (ref "SW2") (pin "3") (pinfunction "PIN3_3") (pintype "passive"))
    )
    (net (code "60") (name "Net-(SW2-PIN4)") (class "Default")
      (node (ref "R47") (pin "1") (pinfunction "1_1") (pintype "passive"))
      (node (ref "SW2") (pin "4") (pinfunction "PIN4_4") (pintype "passive"))
    )
    (net (code "61") (name "Net-(SW2-PIN5)") (class "Default")
      (node (ref "RN1") (pin "5") (pinfunction "5_5") (pintype "passive"))
      (node (ref "SW2") (pin "5") (pinfunction "PIN5_5") (pintype "passive"))
    )
    (net (code "62") (name "Net-(SW2-PIN6)") (class "Default")
      (node (ref "RN1") (pin "6") (pinfunction "6_6") (pintype "passive"))
      (node (ref "SW2") (pin "6") (pinfunction "PIN6_6") (pintype "passive"))
    )
    (net (code "63") (name "Net-(SW2-PIN7)") (class "Default")
      (node (ref "RN1") (pin "7") (pinfunction "7_7") (pintype "passive"))
      (node (ref "SW2") (pin "7") (pinfunction "PIN7_7") (pintype "passive"))
    )
    (net (code "64") (name "Net-(SW2-PIN8)") (class "Default")
      (node (ref "RN1") (pin "8") (pinfunction "8_8") (pintype "passive"))
      (node (ref "SW2") (pin "8") (pinfunction "PIN8_8") (pintype "passive"))
    )
    (net (code "65") (name "Net-(U14-RTC_XTALI)") (class "Default")
      (node (ref "C47") (pin "1") (pinfunction "1_1") (pintype "passive"))
      (node (ref "U14") (pin "T11") (pinfunction "RTC_XTALI_T11") (pintype "passive"))
      (node (ref "X3") (pin "2") (pinfunction "2_2") (pintype "passive"))
    )
    (net (code "66") (name "Net-(U14-RTC_XTALO)") (class "Default")
      (node (ref "C46") (pin "1") (pinfunction "1_1") (pintype "passive"))
      (node (ref "U14") (pin "U11") (pinfunction "RTC_XTALO_U11") (pintype "passive"))
      (node (ref "X3") (pin "1") (pinfunction "1_1") (pintype "passive"))
    )
    (net (code "67") (name "Net-(U14-USDHC1_CLK{slash}GPT2_COMPARE2{slash}SAI2_MCLK{slash}SPDIF_IN{slash}EIM_ADDR20{slash}GPIO2_IO17{slash}USB_OTG1_OC)") (class "Default")
      (node (ref "R40") (pin "2") (pinfunction "2_2") (pintype "passive"))
      (node (ref "U14") (pin "C1") (pinfunction "USDHC1_CLK/GPT2_COMPARE2/SAI2_MCLK/SPDIF_IN/EIM_ADDR20/GPIO2_IO17/USB_OTG1_OC_C1") (pintype "passive"))
    )
    (net (code "68") (name "Net-(U14-VDD_USB_CAP)") (class "Default")
      (node (ref "C116") (pin "2") (pinfunction "2_2") (pintype "passive"))
      (node (ref "C117") (pin "1") (pinfunction "1_1") (pintype "passive"))
      (node (ref "U14") (pin "R12") (pinfunction "VDD_USB_CAP_R12") (pintype "passive"))
    )
    (net (code "69") (name "Net-(U14-XTALI)") (class "Default")
      (node (ref "C49") (pin "2") (pinfunction "2_2") (pintype "passive"))
      (node (ref "R37") (pin "1") (pinfunction "1_1") (pintype "passive"))
      (node (ref "U14") (pin "T16") (pinfunction "XTALI_T16") (pintype "passive"))
      (node (ref "X4") (pin "3") (pinfunction "OSC2_3") (pintype "passive"))
    )
    (net (code "70") (name "Net-(U14-XTALO)") (class "Default")
      (node (ref "C48") (pin "2") (pinfunction "2_2") (pintype "passive"))
      (node (ref "R37") (pin "2") (pinfunction "2_2") (pintype "passive"))
      (node (ref "U14") (pin "T17") (pinfunction "XTALO_T17") (pintype "passive"))
      (node (ref "X4") (pin "1") (pinfunction "OSC1_1") (pintype "passive"))
    )
    (net (code "71") (name "Net-(U15-CANH)") (class "Default")
      (node (ref "R43") (pin "1") (pinfunction "1_1") (pintype "passive"))
      (node (ref "U15") (pin "7") (pinfunction "CANH_7") (pintype "passive"))
    )
    (net (code "72") (name "Net-(U15-CANL)") (class "Default")
      (node (ref "R44") (pin "1") (pinfunction "1_1") (pintype "passive"))
      (node (ref "U15") (pin "6") (pinfunction "CANL_6") (pintype "passive"))
    )
    (net (code "73") (name "Net-(U16-IN)") (class "Default")
      (node (ref "U16") (pin "2") (pinfunction "IN_2") (pintype "passive"))
      (node (ref "WC6") (pin "1") (pinfunction "1_1") (pintype "passive"))
      (node (ref "WC7") (pin "2") (pinfunction "2_2") (pintype "passive"))
      (node (ref "WD2") (pin "2") (pinfunction "K_2") (pintype "passive"))
    )
    (net (code "74") (name "Net-(U17-PIO8)") (class "Default")
      (node (ref "U17") (pin "10") (pinfunction "PIO8_10") (pintype "passive"))
      (node (ref "WR1") (pin "1") (pinfunction "1_1") (pintype "passive"))
    )
    (net (code "75") (name "Net-(U17-PIO11)") (class "Default")
      (node (ref "U17") (pin "13") (pinfunction "PIO11_13") (pintype "passive"))
      (node (ref "WR2") (pin "1") (pinfunction "1_1") (pintype "passive"))
      (node (ref "WSW1") (pin "1") (pinfunction "1_1") (pintype "passive"))
    )
    (net (code "76") (name "Net-(WLED1-A)") (class "Default")
      (node (ref "WLED1") (pin "1") (pinfunction "A_1") (pintype "passive"))
      (node (ref "WR1") (pin "2") (pinfunction "2_2") (pintype "passive"))
    )
    (net (code "77") (name "USB_OTG1_VBUS") (class "Default")
      (node (ref "C107") (pin "1") (pinfunction "1_1") (pintype "passive"))
      (node (ref "U14") (pin "T12") (pinfunction "USB_OTG1_VBUS_T12") (pintype "passive"))
    )
    (net (code "78") (name "USB_OTG2_VBUS") (class "Default")
      (node (ref "C108") (pin "1") (pinfunction "1_1") (pintype "passive"))
      (node (ref "U14") (pin "U12") (pinfunction "USB_OTG2_VBUS_U12") (pintype "passive"))
    )
    (net (code "79") (name "VCC") (class "Default")
      (node (ref "C50") (pin "1") (pinfunction "1_1") (pintype "passive"))
      (node (ref "U15") (pin "3") (pinfunction "VCC_3") (pintype "passive"))
      (node (ref "WD2") (pin "1") (pinfunction "A_1") (pintype "passive"))
    )
    (net (code "80") (name "VCC_3V3") (class "Default")
      (node (ref "R63") (pin "1") (pinfunction "1_1") (pintype "passive"))
    )
    (net (code "81") (name "VCC_SYS") (class "Default")
      (node (ref "R33") (pin "1") (pinfunction "1_1") (pintype "passive"))
      (node (ref "R34") (pin "2") (pinfunction "2_2") (pintype "passive"))
      (node (ref "R35") (pin "2") (pinfunction "2_2") (pintype "passive"))
      (node (ref "R36") (pin "1") (pinfunction "1_1") (pintype "passive"))
      (node (ref "R46") (pin "2") (pinfunction "2_2") (pintype "passive"))
      (node (ref "R47") (pin "2") (pinfunction "2_2") (pintype "passive"))
      (node (ref "RN1") (pin "1") (pinfunction "1_1") (pintype "passive"))
      (node (ref "RN1") (pin "2") (pinfunction "2_2") (pintype "passive"))
      (node (ref "RN1") (pin "3") (pinfunction "3_3") (pintype "passive"))
      (node (ref "RN1") (pin "4") (pinfunction "4_4") (pintype "passive"))
    )
    (net (code "82") (name "unconnected-(U14-CCM_CLK1_N-PadP16)") (class "Default")
      (node (ref "U14") (pin "P16") (pinfunction "CCM_CLK1_N_P16") (pintype "passive+no_connect"))
    )
    (net (code "83") (name "unconnected-(U14-CCM_CLK1_P-PadP17)") (class "Default")
      (node (ref "U14") (pin "P17") (pinfunction "CCM_CLK1_P_P17") (pintype "passive+no_connect"))
    )
    (net (code "84") (name "unconnected-(U14-CCM_PMIC_STBY_REQ-PadU9)") (class "Default")
      (node (ref "U14") (pin "U9") (pinfunction "CCM_PMIC_STBY_REQ_U9") (pintype "passive+no_connect"))
    )
    (net (code "85") (name "unconnected-(U14-GPANAIO-PadR13)") (class "Default")
      (node (ref "U14") (pin "R13") (pinfunction "GPANAIO_R13") (pintype "passive+no_connect"))
    )
    (net (code "86") (name "unconnected-(U14-JTAG_TCK{slash}GPT2_COMPARE2{slash}SAI2_RX_DATA{slash}PWM7_OUT{slash}GPIO1_IO14{slash}SIM2_POWER_FAIL-PadM14)") (class "Default")
      (node (ref "U14") (pin "M14") (pinfunction "JTAG_TCK/GPT2_COMPARE2/SAI2_RX_DATA/PWM7_OUT/GPIO1_IO14/SIM2_POWER_FAIL_M14") (pintype "passive+no_connect"))
    )
    (net (code "87") (name "unconnected-(U14-JTAG_TDI{slash}GPT2_COMPARE1{slash}SAI2_TX_BCLK{slash}PWM6_OUT{slash}GPIO1_IO13{slash}MQS_LEFT{slash}SIM1_POWER_FAIL-PadN16)") (class "Default")
      (node (ref "U14") (pin "N16") (pinfunction "JTAG_TDI/GPT2_COMPARE1/SAI2_TX_BCLK/PWM6_OUT/GPIO1_IO13/MQS_LEFT/SIM1_POWER_FAIL_N16") (pintype "passive+no_connect"))
    )
    (net (code "88") (name "unconnected-(U14-JTAG_TDO{slash}GPT2_CAPTURE2{slash}SAI2_TX_SYNC{slash}CCM_CLKO2{slash}CCM_STOP{slash}GPIO1_IO12{slash}MQS_RIGHT{slash}EPIT2_OUT-PadN15)") (class "Default")
      (node (ref "U14") (pin "N15") (pinfunction "JTAG_TDO/GPT2_CAPTURE2/SAI2_TX_SYNC/CCM_CLKO2/CCM_STOP/GPIO1_IO12/MQS_RIGHT/EPIT2_OUT_N15") (pintype "passive+no_connect"))
    )
    (net (code "89") (name "unconnected-(U14-JTAG_TMS{slash}GPT2_CAPTURE1{slash}SAI2_MCLK{slash}CCM_CLKO1{slash}CCM_WAIT{slash}GPIO1_IO11{slash}SDMA_EXT_EVENT01{slash}EPIT1_OUT-PadP14)") (class "Default")
      (node (ref "U14") (pin "P14") (pinfunction "JTAG_TMS/GPT2_CAPTURE1/SAI2_MCLK/CCM_CLKO1/CCM_WAIT/GPIO1_IO11/SDMA_EXT_EVENT01/EPIT1_OUT_P14") (pintype "passive+no_connect"))
    )
    (net (code "90") (name "unconnected-(U14-JTAG_TRST{slash}GPT2_COMPARE3{slash}SAI2_TX_DATA{slash}PWM8_OUT{slash}GPIO1_IO15{slash}CAAM_RNG_OSC_OBS-PadN14)") (class "Default")
      (node (ref "U14") (pin "N14") (pinfunction "JTAG_TRST/GPT2_COMPARE3/SAI2_TX_DATA/PWM8_OUT/GPIO1_IO15/CAAM_RNG_OSC_OBS_N14") (pintype "passive+no_connect"))
    )
    (net (code "91") (name "unconnected-(U14-SNVS_TAMPER3{slash}GPIO5_IO03-PadP10)") (class "Default")
      (node (ref "U14") (pin "P10") (pinfunction "SNVS_TAMPER3/GPIO5_IO03_P10") (pintype "passive+no_connect"))
    )
    (net (code "92") (name "unconnected-(U14-SNVS_TAMPER6{slash}GPIO5_IO06-PadN11)") (class "Default")
      (node (ref "U14") (pin "N11") (pinfunction "SNVS_TAMPER6/GPIO5_IO06_N11") (pintype "passive+no_connect"))
    )
    (net (code "93") (name "unconnected-(U14-USB_OTG1_CHD#-PadU16)") (class "Default")
      (node (ref "U14") (pin "U16") (pinfunction "USB_OTG1_CHD#_U16") (pintype "passive+no_connect"))
    )
    (net (code "94") (name "unconnected-(U15-VREF-Pad5)") (class "Default")
      (node (ref "U15") (pin "5") (pinfunction "VREF_5") (pintype "passive"))
    )
    (net (code "95") (name "unconnected-(U17-AIO0-Pad17)") (class "Default")
      (node (ref "U17") (pin "17") (pinfunction "AIO0_17") (pintype "passive"))
    )
    (net (code "96") (name "unconnected-(U17-AIO1-Pad18)") (class "Default")
      (node (ref "U17") (pin "18") (pinfunction "AIO1_18") (pintype "passive"))
    )
    (net (code "97") (name "unconnected-(U17-NC-Pad35)") (class "Default")
      (node (ref "U17") (pin "35") (pinfunction "NC_35") (pintype "passive"))
    )
    (net (code "98") (name "unconnected-(U17-PCM-CLK-Pad22)") (class "Default")
      (node (ref "U17") (pin "22") (pinfunction "PCM-CLK_22") (pintype "passive"))
    )
    (net (code "99") (name "unconnected-(U17-PCM-IN-Pad20)") (class "Default")
      (node (ref "U17") (pin "20") (pinfunction "PCM-IN_20") (pintype "passive"))
    )
    (net (code "100") (name "unconnected-(U17-PCM-OUT-Pad21)") (class "Default")
      (node (ref "U17") (pin "21") (pinfunction "PCM-OUT_21") (pintype "passive"))
    )
    (net (code "101") (name "unconnected-(U17-PCM-SYNC-Pad19)") (class "Default")
      (node (ref "U17") (pin "19") (pinfunction "PCM-SYNC_19") (pintype "passive"))
    )
    (net (code "102") (name "unconnected-(U17-PIO0-Pad2)") (class "Default")
      (node (ref "U17") (pin "2") (pinfunction "PIO0_2") (pintype "passive"))
    )
    (net (code "103") (name "unconnected-(U17-PIO1-Pad3)") (class "Default")
      (node (ref "U17") (pin "3") (pinfunction "PIO1_3") (pintype "passive"))
    )
    (net (code "104") (name "unconnected-(U17-PIO2-Pad4)") (class "Default")
      (node (ref "U17") (pin "4") (pinfunction "PIO2_4") (pintype "passive"))
    )
    (net (code "105") (name "unconnected-(U17-PIO3-Pad5)") (class "Default")
      (node (ref "U17") (pin "5") (pinfunction "PIO3_5") (pintype "passive"))
    )
    (net (code "106") (name "unconnected-(U17-PIO4-Pad6)") (class "Default")
      (node (ref "U17") (pin "6") (pinfunction "PIO4_6") (pintype "passive"))
    )
    (net (code "107") (name "unconnected-(U17-PIO5-Pad7)") (class "Default")
      (node (ref "U17") (pin "7") (pinfunction "PIO5_7") (pintype "passive"))
    )
    (net (code "108") (name "unconnected-(U17-PIO6-Pad8)") (class "Default")
      (node (ref "U17") (pin "8") (pinfunction "PIO6_8") (pintype "passive"))
    )
    (net (code "109") (name "unconnected-(U17-PIO7-Pad9)") (class "Default")
      (node (ref "U17") (pin "9") (pinfunction "PIO7_9") (pintype "passive"))
    )
    (net (code "110") (name "unconnected-(U17-PIO9-Pad11)") (class "Default")
      (node (ref "U17") (pin "11") (pinfunction "PIO9_11") (pintype "passive"))
    )
    (net (code "111") (name "unconnected-(U17-PIO10-Pad12)") (class "Default")
      (node (ref "U17") (pin "12") (pinfunction "PIO10_12") (pintype "passive"))
    )
    (net (code "112") (name "unconnected-(U17-RESET-Pad16)") (class "Default")
      (node (ref "U17") (pin "16") (pinfunction "RESET_16") (pintype "passive"))
    )
    (net (code "113") (name "unconnected-(U17-SPI-CLK-Pad30)") (class "Default")
      (node (ref "U17") (pin "30") (pinfunction "SPI-CLK_30") (pintype "passive"))
    )
    (net (code "114") (name "unconnected-(U17-SPI-CSB-Pad33)") (class "Default")
      (node (ref "U17") (pin "33") (pinfunction "SPI-CSB_33") (pintype "passive"))
    )
    (net (code "115") (name "unconnected-(U17-SPI-MISO-Pad32)") (class "Default")
      (node (ref "U17") (pin "32") (pinfunction "SPI-MISO_32") (pintype "passive"))
    )
    (net (code "116") (name "unconnected-(U17-SPI-MOSI-Pad31)") (class "Default")
      (node (ref "U17") (pin "31") (pinfunction "SPI-MOSI_31") (pintype "passive"))
    )
    (net (code "117") (name "unconnected-(U17-UART-CTS-Pad25)") (class "Default")
      (node (ref "U17") (pin "25") (pinfunction "UART-CTS_25") (pintype "passive"))
    )
    (net (code "118") (name "unconnected-(U17-UART-RTS-Pad24)") (class "Default")
      (node (ref "U17") (pin "24") (pinfunction "UART-RTS_24") (pintype "passive"))
    )
    (net (code "119") (name "unconnected-(U17-USB-D--Pad29)") (class "Default")
      (node (ref "U17") (pin "29") (pinfunction "USB-D-_29") (pintype "passive"))
    )
    (net (code "120") (name "unconnected-(U17-USB-D--Pad34)") (class "Default")
      (node (ref "U17") (pin "34") (pinfunction "USB-D-_34") (pintype "passive"))
    )
  )
)
